# v1_0.net
KiCad netlist of a schematic drawn in Altium Designer
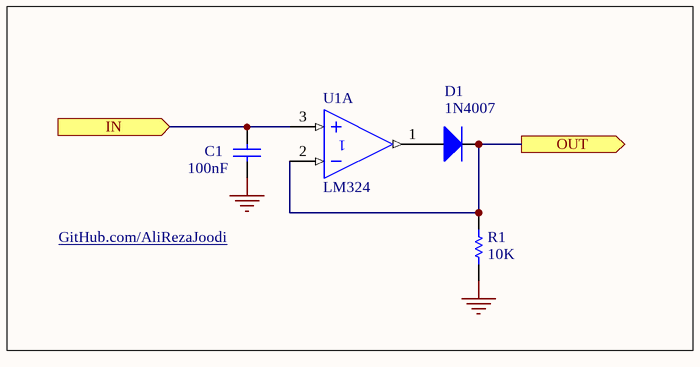
[diagram p0: v1.0.SchDoc]

(export (version "E")
  (design (tool "Eeschema 10.0.6"))
  (components
    (comp (ref "C1")
      (value "100nF")
      (footprint "0805")
      (description "Capacitor")
      (fields (field (name "MANUFACTURER") "Generic Components") (field (name "PUBLISHER") "Altium Limited"))
      (libsource (lib "Miscellaneous Devices") (part "Cap"))
    )
    (comp (ref "D1")
      (value "1N4007")
      (footprint "MELF-D3516-1406")
      (description "Default Diode")
      (fields (field (name "MANUFACTURER") "Generic Components") (field (name "PUBLISHER") "Altium Limited"))
      (libsource (lib "Miscellaneous Devices") (part "Diode"))
    )
    (comp (ref "R1")
      (value "10K")
      (footprint "0805")
      (description "Resistor")
      (fields (field (name "PUBLISHER") "Altium Limited"))
      (libsource (lib "Miscellaneous Devices") (part "Res1"))
    )
    (comp (ref "U1")
      (value "LM324")
      (footprint "SOP127P636-14N")
      (description "Quad Low-Power Operational Amplifier")
      (fields (field (name "PUBLISHER") "Altium Limited"))
      (libsource (lib "my Libraries") (part "LM324"))
    )
  )
  (nets
    (net (code "1") (name "/IN") (class "Default")
      (node (ref "C1") (pin "1") (pinfunction "1_1") (pintype "passive"))
      (node (ref "U1") (pin "3") (pinfunction "IN+_3") (pintype "input"))
    )
    (net (code "2") (name "/OUT") (class "Default")
      (node (ref "D1") (pin "2") (pinfunction "K_2") (pintype "passive"))
      (node (ref "R1") (pin "2") (pinfunction "2_2") (pintype "passive"))
      (node (ref "U1") (pin "2") (pinfunction "IN-_2") (pintype "input"))
    )
    (net (code "3") (name "GND") (class "Default")
      (node (ref "C1") (pin "2") (pinfunction "2_2") (pintype "passive"))
      (node (ref "R1") (pin "1") (pinfunction "1_1") (pintype "passive"))
    )
    (net (code "4") (name "Net-(D1-A)") (class "Default")
      (node (ref "D1") (pin "1") (pinfunction "A_1") (pintype "passive"))
      (node (ref "U1") (pin "1") (pinfunction "OUT_1") (pintype "output"))
    )
  )
)
